# POWER1.net
KiCad netlist of a schematic drawn in Altium Designer
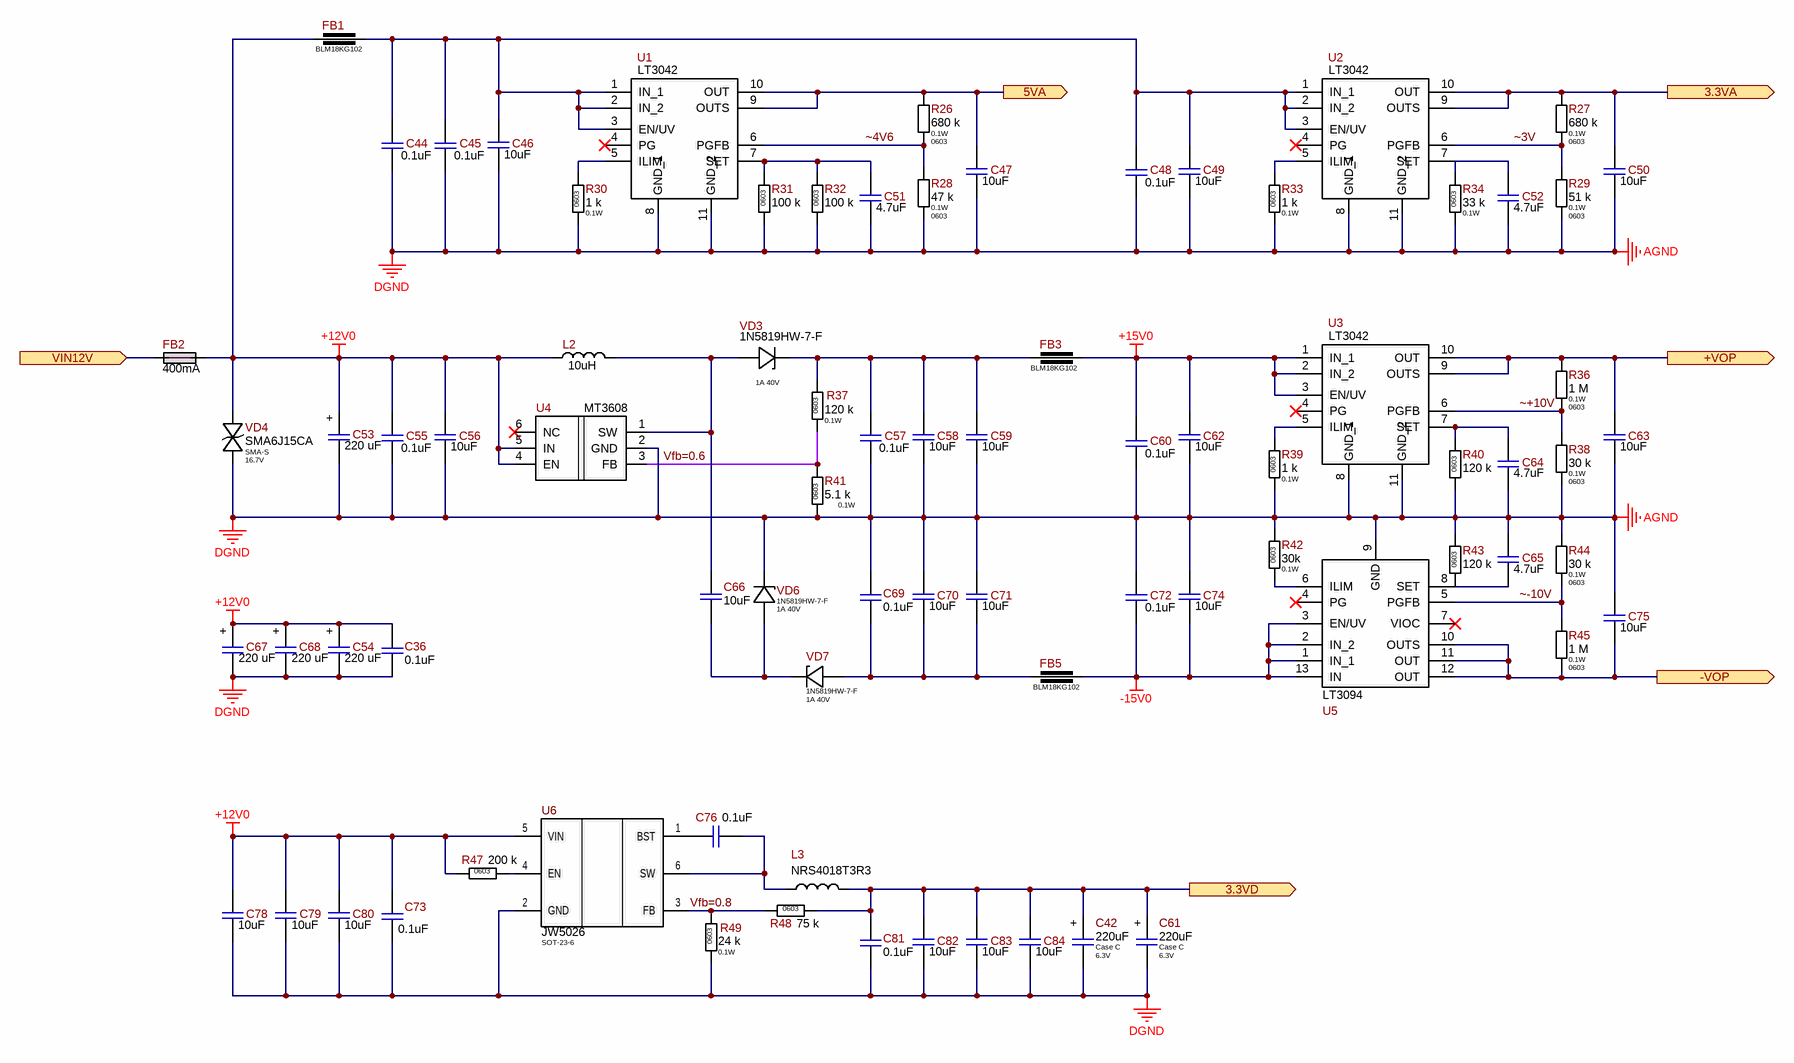
[diagram p0: POWER1.SchDoc]

(export (version "E")
  (design (tool "Eeschema 10.0.6"))
  (components
    (comp (ref "C36")
      (value "0.1uF")
      (footprint "C0805(2012)")
      (description "CAP CER 0.1UF 50V X7R 0805")
      (fields (field (name "PART NUMBER") "0.1uF  50V C0805") (field (name "TOLERANCE") "±10%"))
      (libsource (lib "Database") (part "Capacitor_Ceramic"))
    )
    (comp (ref "C42")
      (value "220uF")
      (footprint "C_TANTAL_CASE_C_MED")
      (description "220uF 6.3V ±10% Case C Tantalum Capacitors RoHS, 70mOhm ESR")
      (fields
        (field (name "PACKAGE") "Case C")
        (field (name "VOLTAGE") "6.3V")
        (field (name "PART NUMBER") "TPSC227K006R0070")
        (field (name "MANUFACTURER") "AVX")
      )
      (libsource (lib "AjaxLibrary") (part "Capacitor-Polar"))
    )
    (comp (ref "C44")
      (value "0.1uF")
      (footprint "C0603(1608)")
      (description "CAP CER 0.1UF 50V X7R 0603")
      (fields (field (name "PART NUMBER") "0.1uF  50V C0603") (field (name "TOLERANCE") "±10%"))
      (libsource (lib "Database") (part "Capacitor_Ceramic"))
    )
    (comp (ref "C45")
      (value "0.1uF")
      (footprint "C0603(1608)")
      (description "CAP CER 0.1UF 50V X7R 0603")
      (fields (field (name "PART NUMBER") "0.1uF  50V C0603") (field (name "TOLERANCE") "±10%"))
      (libsource (lib "Database") (part "Capacitor_Ceramic"))
    )
    (comp (ref "C46")
      (value "10uF")
      (footprint "C0805(2012)")
      (description "CAP CER 10UF 25V X5R 0805")
      (fields (field (name "PART NUMBER") "10uF  25V C0805") (field (name "TOLERANCE") "±10%"))
      (libsource (lib "Database") (part "Capacitor_Ceramic"))
    )
    (comp (ref "C47")
      (value "10uF")
      (footprint "C0805(2012)")
      (description "CAP CER 10UF 25V X5R 0805")
      (fields (field (name "PART NUMBER") "10uF  25V C0805") (field (name "TOLERANCE") "±10%"))
      (libsource (lib "Database") (part "Capacitor_Ceramic"))
    )
    (comp (ref "C48")
      (value "0.1uF")
      (footprint "C0603(1608)")
      (description "CAP CER 0.1UF 50V X7R 0603")
      (fields (field (name "PART NUMBER") "0.1uF  50V C0603") (field (name "TOLERANCE") "±10%"))
      (libsource (lib "Database") (part "Capacitor_Ceramic"))
    )
    (comp (ref "C49")
      (value "10uF")
      (footprint "C0805(2012)")
      (description "CAP CER 10UF 25V X5R 0805")
      (fields (field (name "PART NUMBER") "10uF  25V C0805") (field (name "TOLERANCE") "±10%"))
      (libsource (lib "Database") (part "Capacitor_Ceramic"))
    )
    (comp (ref "C50")
      (value "10uF")
      (footprint "C0805(2012)")
      (description "CAP CER 10UF 25V X5R 0805")
      (fields (field (name "PART NUMBER") "10uF  25V C0805") (field (name "TOLERANCE") "±10%"))
      (libsource (lib "Database") (part "Capacitor_Ceramic"))
    )
    (comp (ref "C51")
      (value "4.7uF")
      (footprint "C0603(1608)")
      (description "CAP CER 4.7UF 25V X6S 0603")
      (fields (field (name "PART NUMBER") "4.7uF  25V C0603") (field (name "TOLERANCE") "±10%"))
      (libsource (lib "Database") (part "Capacitor_Ceramic"))
    )
    (comp (ref "C52")
      (value "4.7uF")
      (footprint "C0603(1608)")
      (description "CAP CER 4.7UF 25V X6S 0603")
      (fields (field (name "PART NUMBER") "4.7uF  25V C0603") (field (name "TOLERANCE") "±10%"))
      (libsource (lib "Database") (part "Capacitor_Ceramic"))
    )
    (comp (ref "C53")
      (value "220 uF")
      (footprint "CAP 8x9")
      (description "CAP POLY 220 UF 20% 16V 8x9")
      (fields (field (name "PART NUMBER") "220 uF  16V 8 x 9") (field (name "TOLERANCE") "±20%"))
      (libsource (lib "Database") (part "Capacitor_Electrolytic"))
    )
    (comp (ref "C54")
      (value "220 uF")
      (footprint "CAP 8x9")
      (description "CAP POLY 220 UF 20% 16V 8x9")
      (fields (field (name "PART NUMBER") "220 uF  16V 8 x 9") (field (name "TOLERANCE") "±20%"))
      (libsource (lib "Database") (part "Capacitor_Electrolytic"))
    )
    (comp (ref "C55")
      (value "0.1uF")
      (footprint "C0805(2012)")
      (description "CAP CER 0.1UF 50V X7R 0805")
      (fields (field (name "PART NUMBER") "0.1uF  50V C0805") (field (name "TOLERANCE") "±10%"))
      (libsource (lib "Database") (part "Capacitor_Ceramic"))
    )
    (comp (ref "C56")
      (value "10uF")
      (footprint "C0805(2012)")
      (description "CAP CER 10UF 25V X5R 0805")
      (fields (field (name "PART NUMBER") "10uF  25V C0805") (field (name "TOLERANCE") "±10%"))
      (libsource (lib "Database") (part "Capacitor_Ceramic"))
    )
    (comp (ref "C57")
      (value "0.1uF")
      (footprint "C0805(2012)")
      (description "CAP CER 0.1UF 50V X7R 0805")
      (fields (field (name "PART NUMBER") "0.1uF  50V C0805") (field (name "TOLERANCE") "±10%"))
      (libsource (lib "Database") (part "Capacitor_Ceramic"))
    )
    (comp (ref "C58")
      (value "10uF")
      (footprint "C0805(2012)")
      (description "CAP CER 10UF 25V X5R 0805")
      (fields (field (name "PART NUMBER") "10uF  25V C0805") (field (name "TOLERANCE") "±10%"))
      (libsource (lib "Database") (part "Capacitor_Ceramic"))
    )
    (comp (ref "C59")
      (value "10uF")
      (footprint "C0805(2012)")
      (description "CAP CER 10UF 25V X5R 0805")
      (fields (field (name "PART NUMBER") "10uF  25V C0805") (field (name "TOLERANCE") "±10%"))
      (libsource (lib "Database") (part "Capacitor_Ceramic"))
    )
    (comp (ref "C60")
      (value "0.1uF")
      (footprint "C0603(1608)")
      (description "CAP CER 0.1UF 50V X7R 0603")
      (fields (field (name "PART NUMBER") "0.1uF  50V C0603") (field (name "TOLERANCE") "±10%"))
      (libsource (lib "Database") (part "Capacitor_Ceramic"))
    )
    (comp (ref "C61")
      (value "220uF")
      (footprint "C_TANTAL_CASE_C_MED")
      (description "220uF 6.3V ±10% Case C Tantalum Capacitors RoHS, 70mOhm ESR")
      (fields
        (field (name "PACKAGE") "Case C")
        (field (name "VOLTAGE") "6.3V")
        (field (name "PART NUMBER") "TPSC227K006R0070")
        (field (name "MANUFACTURER") "AVX")
      )
      (libsource (lib "AjaxLibrary") (part "Capacitor-Polar"))
    )
    (comp (ref "C62")
      (value "10uF")
      (footprint "C0805(2012)")
      (description "CAP CER 10UF 25V X5R 0805")
      (fields (field (name "PART NUMBER") "10uF  25V C0805") (field (name "TOLERANCE") "±10%"))
      (libsource (lib "Database") (part "Capacitor_Ceramic"))
    )
    (comp (ref "C63")
      (value "10uF")
      (footprint "C0805(2012)")
      (description "CAP CER 10UF 25V X5R 0805")
      (fields (field (name "PART NUMBER") "10uF  25V C0805") (field (name "TOLERANCE") "±10%"))
      (libsource (lib "Database") (part "Capacitor_Ceramic"))
    )
    (comp (ref "C64")
      (value "4.7uF")
      (footprint "C0603(1608)")
      (description "CAP CER 4.7UF 25V X6S 0603")
      (fields (field (name "PART NUMBER") "4.7uF  25V C0603") (field (name "TOLERANCE") "±10%"))
      (libsource (lib "Database") (part "Capacitor_Ceramic"))
    )
    (comp (ref "C65")
      (value "4.7uF")
      (footprint "C0603(1608)")
      (description "CAP CER 4.7UF 25V X6S 0603")
      (fields (field (name "PART NUMBER") "4.7uF  25V C0603") (field (name "TOLERANCE") "±10%"))
      (libsource (lib "Database") (part "Capacitor_Ceramic"))
    )
    (comp (ref "C66")
      (value "10uF")
      (footprint "C0805(2012)")
      (description "CAP CER 10UF 25V X5R 0805")
      (fields (field (name "PART NUMBER") "10uF  25V C0805") (field (name "TOLERANCE") "±10%"))
      (libsource (lib "Database") (part "Capacitor_Ceramic"))
    )
    (comp (ref "C67")
      (value "220 uF")
      (footprint "CAP 8x9")
      (description "CAP POLY 220 UF 20% 16V 8x9")
      (fields (field (name "PART NUMBER") "220 uF  16V 8 x 9") (field (name "TOLERANCE") "±20%"))
      (libsource (lib "Database") (part "Capacitor_Electrolytic"))
    )
    (comp (ref "C68")
      (value "220 uF")
      (footprint "CAP 8x9")
      (description "CAP POLY 220 UF 20% 16V 8x9")
      (fields (field (name "PART NUMBER") "220 uF  16V 8 x 9") (field (name "TOLERANCE") "±20%"))
      (libsource (lib "Database") (part "Capacitor_Electrolytic"))
    )
    (comp (ref "C69")
      (value "0.1uF")
      (footprint "C0805(2012)")
      (description "CAP CER 0.1UF 50V X7R 0805")
      (fields (field (name "PART NUMBER") "0.1uF  50V C0805") (field (name "TOLERANCE") "±10%"))
      (libsource (lib "Database") (part "Capacitor_Ceramic"))
    )
    (comp (ref "C70")
      (value "10uF")
      (footprint "C0805(2012)")
      (description "CAP CER 10UF 25V X5R 0805")
      (fields (field (name "PART NUMBER") "10uF  25V C0805") (field (name "TOLERANCE") "±10%"))
      (libsource (lib "Database") (part "Capacitor_Ceramic"))
    )
    (comp (ref "C71")
      (value "10uF")
      (footprint "C0805(2012)")
      (description "CAP CER 10UF 25V X5R 0805")
      (fields (field (name "PART NUMBER") "10uF  25V C0805") (field (name "TOLERANCE") "±10%"))
      (libsource (lib "Database") (part "Capacitor_Ceramic"))
    )
    (comp (ref "C72")
      (value "0.1uF")
      (footprint "C0603(1608)")
      (description "CAP CER 0.1UF 50V X7R 0603")
      (fields (field (name "PART NUMBER") "0.1uF  50V C0603") (field (name "TOLERANCE") "±10%"))
      (libsource (lib "Database") (part "Capacitor_Ceramic"))
    )
    (comp (ref "C73")
      (value "0.1uF")
      (footprint "C0805(2012)")
      (description "CAP CER 0.1UF 50V X7R 0805")
      (fields (field (name "PART NUMBER") "0.1uF  50V C0805") (field (name "TOLERANCE") "±10%"))
      (libsource (lib "Database") (part "Capacitor_Ceramic"))
    )
    (comp (ref "C74")
      (value "10uF")
      (footprint "C0805(2012)")
      (description "CAP CER 10UF 25V X5R 0805")
      (fields (field (name "PART NUMBER") "10uF  25V C0805") (field (name "TOLERANCE") "±10%"))
      (libsource (lib "Database") (part "Capacitor_Ceramic"))
    )
    (comp (ref "C75")
      (value "10uF")
      (footprint "C0805(2012)")
      (description "CAP CER 10UF 25V X5R 0805")
      (fields (field (name "PART NUMBER") "10uF  25V C0805") (field (name "TOLERANCE") "±10%"))
      (libsource (lib "Database") (part "Capacitor_Ceramic"))
    )
    (comp (ref "C76")
      (value "0.1uF")
      (footprint "C0805(2012)")
      (description "CAP CER 0.1UF 50V X7R 0805")
      (fields (field (name "PART NUMBER") "0.1uF  50V C0805") (field (name "TOLERANCE") "±10%"))
      (libsource (lib "Database") (part "Capacitor_Ceramic"))
    )
    (comp (ref "C78")
      (value "10uF")
      (footprint "C0805(2012)")
      (description "CAP CER 10UF 25V X5R 0805")
      (fields (field (name "PART NUMBER") "10uF  25V C0805") (field (name "TOLERANCE") "±10%"))
      (libsource (lib "Database") (part "Capacitor_Ceramic"))
    )
    (comp (ref "C79")
      (value "10uF")
      (footprint "C0805(2012)")
      (description "CAP CER 10UF 25V X5R 0805")
      (fields (field (name "PART NUMBER") "10uF  25V C0805") (field (name "TOLERANCE") "±10%"))
      (libsource (lib "Database") (part "Capacitor_Ceramic"))
    )
    (comp (ref "C80")
      (value "10uF")
      (footprint "C0805(2012)")
      (description "CAP CER 10UF 25V X5R 0805")
      (fields (field (name "PART NUMBER") "10uF  25V C0805") (field (name "TOLERANCE") "±10%"))
      (libsource (lib "Database") (part "Capacitor_Ceramic"))
    )
    (comp (ref "C81")
      (value "0.1uF")
      (footprint "C0805(2012)")
      (description "CAP CER 0.1UF 50V X7R 0805")
      (fields (field (name "PART NUMBER") "0.1uF  50V C0805") (field (name "TOLERANCE") "±10%"))
      (libsource (lib "Database") (part "Capacitor_Ceramic"))
    )
    (comp (ref "C82")
      (value "10uF")
      (footprint "C0805(2012)")
      (description "CAP CER 10UF 25V X5R 0805")
      (fields (field (name "PART NUMBER") "10uF  25V C0805") (field (name "TOLERANCE") "±10%"))
      (libsource (lib "Database") (part "Capacitor_Ceramic"))
    )
    (comp (ref "C83")
      (value "10uF")
      (footprint "C0805(2012)")
      (description "CAP CER 10UF 25V X5R 0805")
      (fields (field (name "PART NUMBER") "10uF  25V C0805") (field (name "TOLERANCE") "±10%"))
      (libsource (lib "Database") (part "Capacitor_Ceramic"))
    )
    (comp (ref "C84")
      (value "10uF")
      (footprint "C0805(2012)")
      (description "CAP CER 10UF 25V X5R 0805")
      (fields (field (name "PART NUMBER") "10uF  25V C0805") (field (name "TOLERANCE") "±10%"))
      (libsource (lib "Database") (part "Capacitor_Ceramic"))
    )
    (comp (ref "FB1")
      (value "BLM18KG102")
      (footprint "BLM18(0603)")
      (description "FERRITE BEAD 1 KOHM 0603 1LN")
      (fields
        (field (name "TOLERANCE") "±25%")
        (field (name "MANUFACTURER") "Murata Electronics North America")
      )
      (libsource (lib "Database") (part "FB"))
    )
    (comp (ref "FB2")
      (value "400mA")
      (footprint "MF-MSMF")
      (description "1812 (4532 Metric), Concave")
      (fields (field (name "MANUFACTURER") "Bourns Inc."))
      (libsource (lib "Database") (part "Resettable_Fuses"))
    )
    (comp (ref "FB3")
      (value "BLM18KG102")
      (footprint "BLM18(0603)")
      (description "FERRITE BEAD 1 KOHM 0603 1LN")
      (fields
        (field (name "TOLERANCE") "±25%")
        (field (name "MANUFACTURER") "Murata Electronics North America")
      )
      (libsource (lib "Database") (part "FB"))
    )
    (comp (ref "FB5")
      (value "BLM18KG102")
      (footprint "BLM18(0603)")
      (description "FERRITE BEAD 1 KOHM 0603 1LN")
      (fields
        (field (name "TOLERANCE") "±25%")
        (field (name "MANUFACTURER") "Murata Electronics North America")
      )
      (libsource (lib "Database") (part "FB"))
    )
    (comp (ref "L2")
      (value "10uH")
      (footprint "WE-LQS SMD 4018")
      (description "FIXED IND 10UH 1A 66 MOHM SMD")
      (fields (field (name "PART NUMBER") "NRS4018T3R3") (field (name "TOLERANCE") "±20"))
      (libsource (lib "Database") (part "INDUCTORS"))
    )
    (comp (ref "L3")
      (value "NRS4018T3R3")
      (footprint "WE-LQS SMD 4018")
      (description "FIXED IND 3.3UH 2A 66 MOHM SMD")
      (fields (field (name "TOLERANCE") "±20") (field (name "MANUFACTURER") "TaiyoYuden"))
      (libsource (lib "Database") (part "INDUCTORS"))
    )
    (comp (ref "R26")
      (value "680 k")
      (footprint "R0603")
      (description "RES SMD 680 k OHM  ±1% 1/10W 0603")
      (fields
        (field (name "POWER RATING") "0.1W")
        (field (name "PACKAGE/CASE") "0603")
        (field (name "PART NUMBER") "680 k  R0603")
        (field (name "TOLERANCE") "±1%")
      )
      (libsource (lib "Database") (part "R0603"))
    )
    (comp (ref "R27")
      (value "680 k")
      (footprint "R0603")
      (description "RES SMD 680 k OHM  ±1% 1/10W 0603")
      (fields
        (field (name "POWER RATING") "0.1W")
        (field (name "PACKAGE/CASE") "0603")
        (field (name "PART NUMBER") "680 k  R0603")
        (field (name "TOLERANCE") "±1%")
      )
      (libsource (lib "Database") (part "R0603"))
    )
    (comp (ref "R28")
      (value "47 k")
      (footprint "R0603")
      (description "RES SMD 47 k OHM  ±1% 1/10W 0603")
      (fields
        (field (name "POWER RATING") "0.1W")
        (field (name "PACKAGE/CASE") "0603")
        (field (name "PART NUMBER") "47 k  R0603")
        (field (name "TOLERANCE") "±1%")
      )
      (libsource (lib "Database") (part "R0603"))
    )
    (comp (ref "R29")
      (value "51 k")
      (footprint "R0603")
      (description "RES SMD 51 k OHM  ±1% 1/10W 0603")
      (fields
        (field (name "POWER RATING") "0.1W")
        (field (name "PACKAGE/CASE") "0603")
        (field (name "PART NUMBER") "51 k  R0603")
        (field (name "TOLERANCE") "±1%")
      )
      (libsource (lib "Database") (part "R0603"))
    )
    (comp (ref "R30")
      (value "1 k")
      (footprint "R0603")
      (description "RES SMD 1 k OHM  ±1% 1/10W 0603")
      (fields
        (field (name "POWER RATING") "0.1W")
        (field (name "PACKAGE/CASE") "0603")
        (field (name "PART NUMBER") "1 k  R0603")
        (field (name "TOLERANCE") "±1%")
      )
      (libsource (lib "Database") (part "R0603"))
    )
    (comp (ref "R31")
      (value "100 k")
      (footprint "R0603")
      (description "RES SMD 100 k OHM  ±1% 1/10W 0603")
      (fields
        (field (name "PACKAGE/CASE") "0603")
        (field (name "PART NUMBER") "100 k  R0603")
        (field (name "TOLERANCE") "±1%")
      )
      (libsource (lib "Database") (part "R0603"))
    )
    (comp (ref "R32")
      (value "100 k")
      (footprint "R0603")
      (description "RES SMD 100 k OHM  ±1% 1/10W 0603")
      (fields
        (field (name "PACKAGE/CASE") "0603")
        (field (name "PART NUMBER") "100 k  R0603")
        (field (name "TOLERANCE") "±1%")
      )
      (libsource (lib "Database") (part "R0603"))
    )
    (comp (ref "R33")
      (value "1 k")
      (footprint "R0603")
      (description "RES SMD 1 k OHM  ±1% 1/10W 0603")
      (fields
        (field (name "POWER RATING") "0.1W")
        (field (name "PACKAGE/CASE") "0603")
        (field (name "PART NUMBER") "1 k  R0603")
        (field (name "TOLERANCE") "±1%")
      )
      (libsource (lib "Database") (part "R0603"))
    )
    (comp (ref "R34")
      (value "33 k")
      (footprint "R0603")
      (description "RES SMD 33 k OHM  ±1% 1/10W 0603")
      (fields
        (field (name "POWER RATING") "0.1W")
        (field (name "PACKAGE/CASE") "0603")
        (field (name "PART NUMBER") "33 k  R0603")
        (field (name "TOLERANCE") "±1%")
      )
      (libsource (lib "Database") (part "R0603"))
    )
    (comp (ref "R36")
      (value "1 M")
      (footprint "R0603")
      (description "RES SMD 1 M OHM  ±1% 1/10W 0603")
      (fields
        (field (name "POWER RATING") "0.1W")
        (field (name "PACKAGE/CASE") "0603")
        (field (name "PART NUMBER") "1 M  R0603")
        (field (name "TOLERANCE") "±1%")
      )
      (libsource (lib "Database") (part "R0603"))
    )
    (comp (ref "R37")
      (value "120 k")
      (footprint "R0603")
      (description "RES SMD 120 k OHM  ±1% 1/10W 0603")
      (fields
        (field (name "POWER RATING") "0.1W")
        (field (name "PACKAGE/CASE") "0603")
        (field (name "PART NUMBER") "120 k  R0603")
        (field (name "TOLERANCE") "±1%")
      )
      (libsource (lib "Database") (part "R0603"))
    )
    (comp (ref "R38")
      (value "30 k")
      (footprint "R0603")
      (description "RES SMD 30 k OHM  ±1% 1/10W 0603")
      (fields
        (field (name "POWER RATING") "0.1W")
        (field (name "PACKAGE/CASE") "0603")
        (field (name "PART NUMBER") "30 k  R0603")
        (field (name "TOLERANCE") "±1%")
      )
      (libsource (lib "Database") (part "R0603"))
    )
    (comp (ref "R39")
      (value "1 k")
      (footprint "R0603")
      (description "RES SMD 1 k OHM  ±1% 1/10W 0603")
      (fields
        (field (name "POWER RATING") "0.1W")
        (field (name "PACKAGE/CASE") "0603")
        (field (name "PART NUMBER") "1 k  R0603")
        (field (name "TOLERANCE") "±1%")
      )
      (libsource (lib "Database") (part "R0603"))
    )
    (comp (ref "R40")
      (value "120 k")
      (footprint "R0603")
      (description "RES SMD 120 k OHM  ±1% 1/10W 0603")
      (fields
        (field (name "PACKAGE/CASE") "0603")
        (field (name "PART NUMBER") "120 k  R0603")
        (field (name "TOLERANCE") "±1%")
      )
      (libsource (lib "Database") (part "R0603"))
    )
    (comp (ref "R41")
      (value "5.1 k")
      (footprint "R0603")
      (description "RES SMD 5.1 k OHM  ±1% 1/10W 0603")
      (fields
        (field (name "PACKAGE/CASE") "0603")
        (field (name "POWER RATING") "0.1W")
        (field (name "PART NUMBER") "5.1 k  R0603")
        (field (name "TOLERANCE") "±1%")
      )
      (libsource (lib "Database") (part "R0603"))
    )
    (comp (ref "R42")
      (value "30k")
      (footprint "R0603")
      (description "RES SMD 120 k OHM  ±1% 1/10W 0603")
      (fields
        (field (name "POWER RATING") "0.1W")
        (field (name "PACKAGE/CASE") "0603")
        (field (name "PART NUMBER") "120 k  R0603")
        (field (name "TOLERANCE") "±1%")
      )
      (libsource (lib "Database") (part "R0603"))
    )
    (comp (ref "R43")
      (value "120 k")
      (footprint "R0603")
      (description "RES SMD 120 k OHM  ±1% 1/10W 0603")
      (fields
        (field (name "PACKAGE/CASE") "0603")
        (field (name "PART NUMBER") "120 k  R0603")
        (field (name "TOLERANCE") "±1%")
      )
      (libsource (lib "Database") (part "R0603"))
    )
    (comp (ref "R44")
      (value "30 k")
      (footprint "R0603")
      (description "RES SMD 30 k OHM  ±1% 1/10W 0603")
      (fields
        (field (name "POWER RATING") "0.1W")
        (field (name "PACKAGE/CASE") "0603")
        (field (name "PART NUMBER") "30 k  R0603")
        (field (name "TOLERANCE") "±1%")
      )
      (libsource (lib "Database") (part "R0603"))
    )
    (comp (ref "R45")
      (value "1 M")
      (footprint "R0603")
      (description "RES SMD 1 M OHM  ±1% 1/10W 0603")
      (fields
        (field (name "POWER RATING") "0.1W")
        (field (name "PACKAGE/CASE") "0603")
        (field (name "PART NUMBER") "1 M  R0603")
        (field (name "TOLERANCE") "±1%")
      )
      (libsource (lib "Database") (part "R0603"))
    )
    (comp (ref "R47")
      (value "200 k")
      (footprint "R0603")
      (description "RES SMD 200 k OHM  ±1% 1/10W 0603")
      (fields
        (field (name "PACKAGE/CASE") "0603")
        (field (name "PART NUMBER") "200 k  R0603")
        (field (name "TOLERANCE") "±1%")
      )
      (libsource (lib "Database") (part "R0603"))
    )
    (comp (ref "R48")
      (value "75 k")
      (footprint "R0603")
      (description "RES SMD 75 k OHM  ±1% 1/10W 0603")
      (fields
        (field (name "PACKAGE/CASE") "0603")
        (field (name "PART NUMBER") "75 k  R0603")
        (field (name "TOLERANCE") "±1%")
      )
      (libsource (lib "Database") (part "R0603"))
    )
    (comp (ref "R49")
      (value "24 k")
      (footprint "R0603")
      (description "RES SMD 24 k OHM  ±1% 1/10W 0603")
      (fields
        (field (name "POWER RATING") "0.1W")
        (field (name "PACKAGE/CASE") "0603")
        (field (name "PART NUMBER") "24 k  R0603")
        (field (name "TOLERANCE") "±1%")
      )
      (libsource (lib "Database") (part "R0603"))
    )
    (comp (ref "U1")
      (value "LT3042")
      (footprint "MSOP-10-EP")
      (fields
        (field (name "MANUFACTURER_PART_NUMBER") "LT3042IMSE#PBF")
        (field (name "MOUSER PART NUMBER") "584-LT3042IMSE#PBF")
      )
      (libsource (lib "Database") (part "LT3042"))
    )
    (comp (ref "U2")
      (value "LT3042")
      (footprint "MSOP-10-EP")
      (fields
        (field (name "MANUFACTURER_PART_NUMBER") "LT3042IMSE#PBF")
        (field (name "MOUSER PART NUMBER") "584-LT3042IMSE#PBF")
      )
      (libsource (lib "Database") (part "LT3042"))
    )
    (comp (ref "U3")
      (value "LT3042")
      (footprint "MSOP-10-EP")
      (fields
        (field (name "MANUFACTURER_PART_NUMBER") "LT3042IMSE#PBF")
        (field (name "MOUSER PART NUMBER") "584-LT3042IMSE#PBF")
      )
      (libsource (lib "Database") (part "LT3042"))
    )
    (comp (ref "U4")
      (value "MT3608")
      (footprint "SOT23-6")
      (description "HIGH EFFICIENCY 1.2MHZ 2A STEP UP CONVERTER")
      (fields (field (name "MANUFACTURER") "AEROSEMI"))
      (libsource (lib "Database") (part "MT3608"))
    )
    (comp (ref "U5")
      (value "LT3094")
      (footprint "DFN-12")
      (fields
        (field (name "MANUFACTURER_PART_NUMBER") "LT3042IMSE#PBF")
        (field (name "MOUSER PART NUMBER") "584-LT3042IMSE#PBF")
        (field (name "MANUFACTURER") "Analog Devices Inc.")
      )
      (libsource (lib "Database") (part "LT3094"))
    )
    (comp (ref "U6")
      (value "JW5026")
      (footprint "SOT23-6")
      (fields (field (name "PACKAGE") "SOT-23-6") (field (name "MANUFACTURER") "Joulwatt Technology"))
      (libsource (lib "Database") (part "JW5026"))
    )
    (comp (ref "VD3")
      (value "1N5819HW-7-F")
      (footprint "SOD-123")
      (description "DIODE SCHOTTKY 40V 1A SOD-123")
      (fields (field (name "POWER RATING") "1A 40V") (field (name "MANUFACTURER") "Diodes Incorporated"))
      (libsource (lib "Database") (part "SCHOTTKY"))
    )
    (comp (ref "VD4")
      (value "SMA6J15CA")
      (footprint "SMA-S-Bi1-ST_MED")
      (description "TVS Diode 24.4V Clamp, 24.6A (10/1000us) Ipp, SMA-S")
      (fields
        (field (name "PART NUMBER") "SMA6J15CA")
        (field (name "PACKAGE") "SMA-S")
        (field (name "VOLTAGE") "16.7V")
        (field (name "MANUFACTURER") "Bourns")
      )
      (libsource (lib "AjaxLibrary") (part "Diode-TVS-Bi-1"))
    )
    (comp (ref "VD6")
      (value "1N5819HW-7-F")
      (footprint "SOD-123")
      (description "DIODE SCHOTTKY 40V 1A SOD-123")
      (fields (field (name "POWER RATING") "1A 40V") (field (name "MANUFACTURER") "Diodes Incorporated"))
      (libsource (lib "Database") (part "SCHOTTKY"))
    )
    (comp (ref "VD7")
      (value "1N5819HW-7-F")
      (footprint "SOD-123")
      (description "DIODE SCHOTTKY 40V 1A SOD-123")
      (fields (field (name "POWER RATING") "1A 40V") (field (name "MANUFACTURER") "Diodes Incorporated"))
      (libsource (lib "Database") (part "SCHOTTKY"))
    )
  )
  (nets
    (net (code "1") (name "+12V0") (class "Default")
      (node (ref "C36") (pin "2") (pinfunction "2_2") (pintype "passive"))
      (node (ref "C53") (pin "1") (pinfunction "1_1") (pintype "passive"))
      (node (ref "C54") (pin "1") (pinfunction "1_1") (pintype "passive"))
      (node (ref "C55") (pin "2") (pinfunction "2_2") (pintype "passive"))
      (node (ref "C56") (pin "1") (pinfunction "1_1") (pintype "passive"))
      (node (ref "C67") (pin "1") (pinfunction "1_1") (pintype "passive"))
      (node (ref "C68") (pin "1") (pinfunction "1_1") (pintype "passive"))
      (node (ref "C73") (pin "2") (pinfunction "2_2") (pintype "passive"))
      (node (ref "C78") (pin "1") (pinfunction "1_1") (pintype "passive"))
      (node (ref "C79") (pin "1") (pinfunction "1_1") (pintype "passive"))
      (node (ref "C80") (pin "1") (pinfunction "1_1") (pintype "passive"))
      (node (ref "FB1") (pin "1") (pintype "passive"))
      (node (ref "FB2") (pin "2") (pinfunction "2_2") (pintype "passive"))
      (node (ref "L2") (pin "1") (pintype "passive"))
      (node (ref "R47") (pin "1") (pinfunction "1_1") (pintype "passive"))
      (node (ref "U4") (pin "4") (pinfunction "EN_4") (pintype "passive"))
      (node (ref "U4") (pin "5") (pinfunction "IN_5") (pintype "passive"))
      (node (ref "U6") (pin "5") (pinfunction "VIN_5") (pintype "passive"))
      (node (ref "VD4") (pin "AN1") (pinfunction "AN1_AN1") (pintype "passive"))
    )
    (net (code "2") (name "+15V0") (class "Default")
      (node (ref "C60") (pin "2") (pinfunction "2_2") (pintype "passive"))
      (node (ref "C62") (pin "1") (pinfunction "1_1") (pintype "passive"))
      (node (ref "FB3") (pin "2") (pintype "passive"))
      (node (ref "U3") (pin "1") (pinfunction "IN_1_1") (pintype "passive"))
      (node (ref "U3") (pin "2") (pinfunction "IN_2_2") (pintype "passive"))
      (node (ref "U3") (pin "3") (pinfunction "EN/UV_3") (pintype "passive"))
    )
    (net (code "3") (name "-15V0") (class "Default")
      (node (ref "C72") (pin "1") (pinfunction "1_1") (pintype "passive"))
      (node (ref "C74") (pin "2") (pinfunction "2_2") (pintype "passive"))
      (node (ref "FB5") (pin "2") (pintype "passive"))
      (node (ref "U5") (pin "1") (pinfunction "IN_1_1") (pintype "passive"))
      (node (ref "U5") (pin "13") (pinfunction "IN_13") (pintype "passive"))
      (node (ref "U5") (pin "2") (pinfunction "IN_2_2") (pintype "passive"))
      (node (ref "U5") (pin "3") (pinfunction "EN/UV_3") (pintype "passive"))
    )
    (net (code "4") (name "/+VOP") (class "Default")
      (node (ref "C63") (pin "1") (pinfunction "1_1") (pintype "passive"))
      (node (ref "R36") (pin "1") (pinfunction "1_1") (pintype "passive"))
      (node (ref "U3") (pin "10") (pinfunction "OUT_10") (pintype "passive"))
      (node (ref "U3") (pin "9") (pinfunction "OUTS_9") (pintype "passive"))
    )
    (net (code "5") (name "/-VOP") (class "Default")
      (node (ref "C75") (pin "2") (pinfunction "2_2") (pintype "passive"))
      (node (ref "R45") (pin "2") (pinfunction "2_2") (pintype "passive"))
      (node (ref "U5") (pin "10") (pinfunction "OUTS_10") (pintype "passive"))
      (node (ref "U5") (pin "11") (pinfunction "OUT_11") (pintype "passive"))
      (node (ref "U5") (pin "12") (pinfunction "OUT_12") (pintype "passive"))
    )
    (net (code "6") (name "/3.3VA") (class "Default")
      (node (ref "C50") (pin "1") (pinfunction "1_1") (pintype "passive"))
      (node (ref "R27") (pin "2") (pinfunction "2_2") (pintype "passive"))
      (node (ref "U2") (pin "10") (pinfunction "OUT_10") (pintype "passive"))
      (node (ref "U2") (pin "9") (pinfunction "OUTS_9") (pintype "passive"))
    )
    (net (code "7") (name "/3.3VD") (class "Default")
      (node (ref "C42") (pin "1") (pinfunction "1_1") (pintype "passive"))
      (node (ref "C61") (pin "1") (pinfunction "1_1") (pintype "passive"))
      (node (ref "C81") (pin "2") (pinfunction "2_2") (pintype "passive"))
      (node (ref "C82") (pin "1") (pinfunction "1_1") (pintype "passive"))
      (node (ref "C83") (pin "1") (pinfunction "1_1") (pintype "passive"))
      (node (ref "C84") (pin "1") (pinfunction "1_1") (pintype "passive"))
      (node (ref "L3") (pin "2") (pintype "passive"))
      (node (ref "R48") (pin "2") (pinfunction "2_2") (pintype "passive"))
    )
    (net (code "8") (name "/5VA") (class "Default")
      (node (ref "C47") (pin "1") (pinfunction "1_1") (pintype "passive"))
      (node (ref "R26") (pin "2") (pinfunction "2_2") (pintype "passive"))
      (node (ref "U1") (pin "10") (pinfunction "OUT_10") (pintype "passive"))
      (node (ref "U1") (pin "9") (pinfunction "OUTS_9") (pintype "passive"))
    )
    (net (code "9") (name "/VIN12V") (class "Default")
      (node (ref "FB2") (pin "1") (pinfunction "1_1") (pintype "passive"))
    )
    (net (code "10") (name "/Vfb=0.6") (class "Default")
      (node (ref "R37") (pin "1") (pinfunction "1_1") (pintype "passive"))
      (node (ref "R41") (pin "2") (pinfunction "2_2") (pintype "passive"))
      (node (ref "U4") (pin "3") (pinfunction "FB_3") (pintype "passive"))
    )
    (net (code "11") (name "/Vfb=0.8") (class "Default")
      (node (ref "R48") (pin "1") (pinfunction "1_1") (pintype "passive"))
      (node (ref "R49") (pin "2") (pinfunction "2_2") (pintype "passive"))
      (node (ref "U6") (pin "3") (pinfunction "FB_3") (pintype "passive"))
    )
    (net (code "12") (name "/~+10V") (class "Default")
      (node (ref "R36") (pin "2") (pinfunction "2_2") (pintype "passive"))
      (node (ref "R38") (pin "1") (pinfunction "1_1") (pintype "passive"))
      (node (ref "U3") (pin "6") (pinfunction "PGFB_6") (pintype "passive"))
    )
    (net (code "13") (name "/~-10V") (class "Default")
      (node (ref "R44") (pin "2") (pinfunction "2_2") (pintype "passive"))
      (node (ref "R45") (pin "1") (pinfunction "1_1") (pintype "passive"))
      (node (ref "U5") (pin "5") (pinfunction "PGFB_5") (pintype "passive"))
    )
    (net (code "14") (name "/~3V") (class "Default")
      (node (ref "R27") (pin "1") (pinfunction "1_1") (pintype "passive"))
      (node (ref "R29") (pin "2") (pinfunction "2_2") (pintype "passive"))
      (node (ref "U2") (pin "6") (pinfunction "PGFB_6") (pintype "passive"))
    )
    (net (code "15") (name "/~4V6") (class "Default")
      (node (ref "R26") (pin "1") (pinfunction "1_1") (pintype "passive"))
      (node (ref "R28") (pin "2") (pinfunction "2_2") (pintype "passive"))
      (node (ref "U1") (pin "6") (pinfunction "PGFB_6") (pintype "passive"))
    )
    (net (code "16") (name "AGND") (class "Default")
      (node (ref "C36") (pin "1") (pinfunction "1_1") (pintype "passive"))
      (node (ref "C42") (pin "2") (pinfunction "2_2") (pintype "passive"))
      (node (ref "C44") (pin "1") (pinfunction "1_1") (pintype "passive"))
      (node (ref "C45") (pin "1") (pinfunction "1_1") (pintype "passive"))
      (node (ref "C46") (pin "2") (pinfunction "2_2") (pintype "passive"))
      (node (ref "C47") (pin "2") (pinfunction "2_2") (pintype "passive"))
      (node (ref "C48") (pin "1") (pinfunction "1_1") (pintype "passive"))
      (node (ref "C49") (pin "2") (pinfunction "2_2") (pintype "passive"))
      (node (ref "C50") (pin "2") (pinfunction "2_2") (pintype "passive"))
      (node (ref "C51") (pin "2") (pinfunction "2_2") (pintype "passive"))
      (node (ref "C52") (pin "2") (pinfunction "2_2") (pintype "passive"))
      (node (ref "C53") (pin "2") (pinfunction "2_2") (pintype "passive"))
      (node (ref "C54") (pin "2") (pinfunction "2_2") (pintype "passive"))
      (node (ref "C55") (pin "1") (pinfunction "1_1") (pintype "passive"))
      (node (ref "C56") (pin "2") (pinfunction "2_2") (pintype "passive"))
      (node (ref "C57") (pin "1") (pinfunction "1_1") (pintype "passive"))
      (node (ref "C58") (pin "2") (pinfunction "2_2") (pintype "passive"))
      (node (ref "C59") (pin "2") (pinfunction "2_2") (pintype "passive"))
      (node (ref "C60") (pin "1") (pinfunction "1_1") (pintype "passive"))
      (node (ref "C61") (pin "2") (pinfunction "2_2") (pintype "passive"))
      (node (ref "C62") (pin "2") (pinfunction "2_2") (pintype "passive"))
      (node (ref "C63") (pin "2") (pinfunction "2_2") (pintype "passive"))
      (node (ref "C64") (pin "2") (pinfunction "2_2") (pintype "passive"))
      (node (ref "C65") (pin "1") (pinfunction "1_1") (pintype "passive"))
      (node (ref "C67") (pin "2") (pinfunction "2_2") (pintype "passive"))
      (node (ref "C68") (pin "2") (pinfunction "2_2") (pintype "passive"))
      (node (ref "C69") (pin "2") (pinfunction "2_2") (pintype "passive"))
      (node (ref "C70") (pin "1") (pinfunction "1_1") (pintype "passive"))
      (node (ref "C71") (pin "1") (pinfunction "1_1") (pintype "passive"))
      (node (ref "C72") (pin "2") (pinfunction "2_2") (pintype "passive"))
      (node (ref "C73") (pin "1") (pinfunction "1_1") (pintype "passive"))
      (node (ref "C74") (pin "1") (pinfunction "1_1") (pintype "passive"))
      (node (ref "C75") (pin "1") (pinfunction "1_1") (pintype "passive"))
      (node (ref "C78") (pin "2") (pinfunction "2_2") (pintype "passive"))
      (node (ref "C79") (pin "2") (pinfunction "2_2") (pintype "passive"))
      (node (ref "C80") (pin "2") (pinfunction "2_2") (pintype "passive"))
      (node (ref "C81") (pin "1") (pinfunction "1_1") (pintype "passive"))
      (node (ref "C82") (pin "2") (pinfunction "2_2") (pintype "passive"))
      (node (ref "C83") (pin "2") (pinfunction "2_2") (pintype "passive"))
      (node (ref "C84") (pin "2") (pinfunction "2_2") (pintype "passive"))
      (node (ref "R28") (pin "1") (pinfunction "1_1") (pintype "passive"))
      (node (ref "R29") (pin "1") (pinfunction "1_1") (pintype "passive"))
      (node (ref "R30") (pin "1") (pinfunction "1_1") (pintype "passive"))
      (node (ref "R31") (pin "1") (pinfunction "1_1") (pintype "passive"))
      (node (ref "R32") (pin "1") (pinfunction "1_1") (pintype "passive"))
      (node (ref "R33") (pin "1") (pinfunction "1_1") (pintype "passive"))
      (node (ref "R34") (pin "1") (pinfunction "1_1") (pintype "passive"))
      (node (ref "R38") (pin "2") (pinfunction "2_2") (pintype "passive"))
      (node (ref "R39") (pin "1") (pinfunction "1_1") (pintype "passive"))
      (node (ref "R40") (pin "1") (pinfunction "1_1") (pintype "passive"))
      (node (ref "R41") (pin "1") (pinfunction "1_1") (pintype "passive"))
      (node (ref "R42") (pin "2") (pinfunction "2_2") (pintype "passive"))
      (node (ref "R43") (pin "2") (pinfunction "2_2") (pintype "passive"))
      (node (ref "R44") (pin "1") (pinfunction "1_1") (pintype "passive"))
      (node (ref "R49") (pin "1") (pinfunction "1_1") (pintype "passive"))
      (node (ref "U1") (pin "11") (pinfunction "GND_2_11") (pintype "passive"))
      (node (ref "U1") (pin "8") (pinfunction "GND_1_8") (pintype "passive"))
      (node (ref "U2") (pin "11") (pinfunction "GND_2_11") (pintype "passive"))
      (node (ref "U2") (pin "8") (pinfunction "GND_1_8") (pintype "passive"))
      (node (ref "U3") (pin "11") (pinfunction "GND_2_11") (pintype "passive"))
      (node (ref "U3") (pin "8") (pinfunction "GND_1_8") (pintype "passive"))
      (node (ref "U4") (pin "2") (pinfunction "GND_2") (pintype "power_in"))
      (node (ref "U5") (pin "9") (pinfunction "GND_9") (pintype "passive"))
      (node (ref "U6") (pin "2") (pinfunction "GND_2") (pintype "passive"))
      (node (ref "VD4") (pin "AN2") (pinfunction "AN2_AN2") (pintype "passive"))
      (node (ref "VD6") (pin "1") (pinfunction "K_1") (pintype "passive"))
    )
    (net (code "17") (name "Net-(U1-EN{slash}UV)") (class "Default")
      (node (ref "C44") (pin "2") (pinfunction "2_2") (pintype "passive"))
      (node (ref "C45") (pin "2") (pinfunction "2_2") (pintype "passive"))
      (node (ref "C46") (pin "1") (pinfunction "1_1") (pintype "passive"))
      (node (ref "C48") (pin "2") (pinfunction "2_2") (pintype "passive"))
      (node (ref "C49") (pin "1") (pinfunction "1_1") (pintype "passive"))
      (node (ref "FB1") (pin "2") (pintype "passive"))
      (node (ref "U1") (pin "1") (pinfunction "IN_1_1") (pintype "passive"))
      (node (ref "U1") (pin "2") (pinfunction "IN_2_2") (pintype "passive"))
      (node (ref "U1") (pin "3") (pinfunction "EN/UV_3") (pintype "passive"))
      (node (ref "U2") (pin "1") (pinfunction "IN_1_1") (pintype "passive"))
      (node (ref "U2") (pin "2") (pinfunction "IN_2_2") (pintype "passive"))
      (node (ref "U2") (pin "3") (pinfunction "EN/UV_3") (pintype "passive"))
    )
    (net (code "18") (name "Net-(U1-ILIM)") (class "Default")
      (node (ref "R30") (pin "2") (pinfunction "2_2") (pintype "passive"))
      (node (ref "U1") (pin "5") (pinfunction "ILIM_5") (pintype "passive"))
    )
    (net (code "19") (name "Net-(U1-SET)") (class "Default")
      (node (ref "C51") (pin "1") (pinfunction "1_1") (pintype "passive"))
      (node (ref "R31") (pin "2") (pinfunction "2_2") (pintype "passive"))
      (node (ref "R32") (pin "2") (pinfunction "2_2") (pintype "passive"))
      (node (ref "U1") (pin "7") (pinfunction "SET_7") (pintype "passive"))
    )
    (net (code "20") (name "Net-(U2-ILIM)") (class "Default")
      (node (ref "R33") (pin "2") (pinfunction "2_2") (pintype "passive"))
      (node (ref "U2") (pin "5") (pinfunction "ILIM_5") (pintype "passive"))
    )
    (net (code "21") (name "Net-(U2-SET)") (class "Default")
      (node (ref "C52") (pin "1") (pinfunction "1_1") (pintype "passive"))
      (node (ref "R34") (pin "2") (pinfunction "2_2") (pintype "passive"))
      (node (ref "U2") (pin "7") (pinfunction "SET_7") (pintype "passive"))
    )
    (net (code "22") (name "Net-(U3-ILIM)") (class "Default")
      (node (ref "R39") (pin "2") (pinfunction "2_2") (pintype "passive"))
      (node (ref "U3") (pin "5") (pinfunction "ILIM_5") (pintype "passive"))
    )
    (net (code "23") (name "Net-(U3-SET)") (class "Default")
      (node (ref "C64") (pin "1") (pinfunction "1_1") (pintype "passive"))
      (node (ref "R40") (pin "2") (pinfunction "2_2") (pintype "passive"))
      (node (ref "U3") (pin "7") (pinfunction "SET_7") (pintype "passive"))
    )
    (net (code "24") (name "Net-(U4-SW)") (class "Default")
      (node (ref "C66") (pin "1") (pinfunction "1_1") (pintype "passive"))
      (node (ref "L2") (pin "2") (pintype "passive"))
      (node (ref "U4") (pin "1") (pinfunction "SW_1") (pintype "power_in"))
      (node (ref "VD3") (pin "2") (pinfunction "A_2") (pintype "passive"))
    )
    (net (code "25") (name "Net-(U5-ILIM)") (class "Default")
      (node (ref "R42") (pin "1") (pinfunction "1_1") (pintype "passive"))
      (node (ref "U5") (pin "6") (pinfunction "ILIM_6") (pintype "passive"))
    )
    (net (code "26") (name "Net-(U5-SET)") (class "Default")
      (node (ref "C65") (pin "2") (pinfunction "2_2") (pintype "passive"))
      (node (ref "R43") (pin "1") (pinfunction "1_1") (pintype "passive"))
      (node (ref "U5") (pin "8") (pinfunction "SET_8") (pintype "passive"))
    )
    (net (code "27") (name "Net-(U6-BST)") (class "Default")
      (node (ref "C76") (pin "1") (pinfunction "1_1") (pintype "passive"))
      (node (ref "U6") (pin "1") (pinfunction "BST_1") (pintype "passive"))
    )
    (net (code "28") (name "Net-(U6-EN)") (class "Default")
      (node (ref "R47") (pin "2") (pinfunction "2_2") (pintype "passive"))
      (node (ref "U6") (pin "4") (pinfunction "EN_4") (pintype "passive"))
    )
    (net (code "29") (name "Net-(U6-SW)") (class "Default")
      (node (ref "C76") (pin "2") (pinfunction "2_2") (pintype "passive"))
      (node (ref "L3") (pin "1") (pintype "passive"))
      (node (ref "U6") (pin "6") (pinfunction "SW_6") (pintype "passive"))
    )
    (net (code "30") (name "Net-(VD3-K)") (class "Default")
      (node (ref "C57") (pin "2") (pinfunction "2_2") (pintype "passive"))
      (node (ref "C58") (pin "1") (pinfunction "1_1") (pintype "passive"))
      (node (ref "C59") (pin "1") (pinfunction "1_1") (pintype "passive"))
      (node (ref "FB3") (pin "1") (pintype "passive"))
      (node (ref "R37") (pin "2") (pinfunction "2_2") (pintype "passive"))
      (node (ref "VD3") (pin "1") (pinfunction "K_1") (pintype "passive"))
    )
    (net (code "31") (name "Net-(VD6-A)") (class "Default")
      (node (ref "C66") (pin "2") (pinfunction "2_2") (pintype "passive"))
      (node (ref "VD6") (pin "2") (pinfunction "A_2") (pintype "passive"))
      (node (ref "VD7") (pin "1") (pinfunction "K_1") (pintype "passive"))
    )
    (net (code "32") (name "Net-(VD7-A)") (class "Default")
      (node (ref "C69") (pin "1") (pinfunction "1_1") (pintype "passive"))
      (node (ref "C70") (pin "2") (pinfunction "2_2") (pintype "passive"))
      (node (ref "C71") (pin "2") (pinfunction "2_2") (pintype "passive"))
      (node (ref "FB5") (pin "1") (pintype "passive"))
      (node (ref "VD7") (pin "2") (pinfunction "A_2") (pintype "passive"))
    )
    (net (code "33") (name "unconnected-(U1-PG-Pad4)") (class "Default")
      (node (ref "U1") (pin "4") (pinfunction "PG_4") (pintype "passive+no_connect"))
    )
    (net (code "34") (name "unconnected-(U2-PG-Pad4)") (class "Default")
      (node (ref "U2") (pin "4") (pinfunction "PG_4") (pintype "passive+no_connect"))
    )
    (net (code "35") (name "unconnected-(U3-PG-Pad4)") (class "Default")
      (node (ref "U3") (pin "4") (pinfunction "PG_4") (pintype "passive+no_connect"))
    )
    (net (code "36") (name "unconnected-(U4-NC-Pad6)") (class "Default")
      (node (ref "U4") (pin "6") (pinfunction "NC_6") (pintype "passive+no_connect"))
    )
    (net (code "37") (name "unconnected-(U5-PG-Pad4)") (class "Default")
      (node (ref "U5") (pin "4") (pinfunction "PG_4") (pintype "passive+no_connect"))
    )
    (net (code "38") (name "unconnected-(U5-VIOC-Pad7)") (class "Default")
      (node (ref "U5") (pin "7") (pinfunction "VIOC_7") (pintype "passive+no_connect"))
    )
  )
)
